# sliit_2019_V3.net
KiCad netlist of a schematic drawn in EAGLE
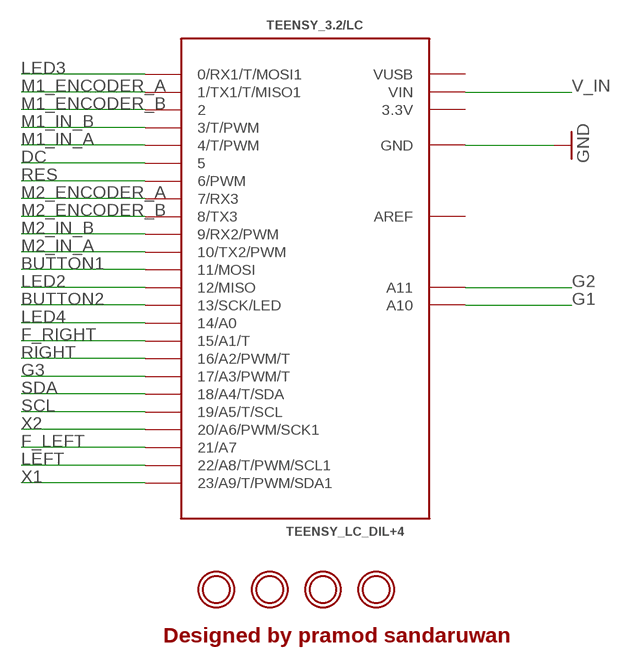
[diagram p0: schematic, sheet 1]
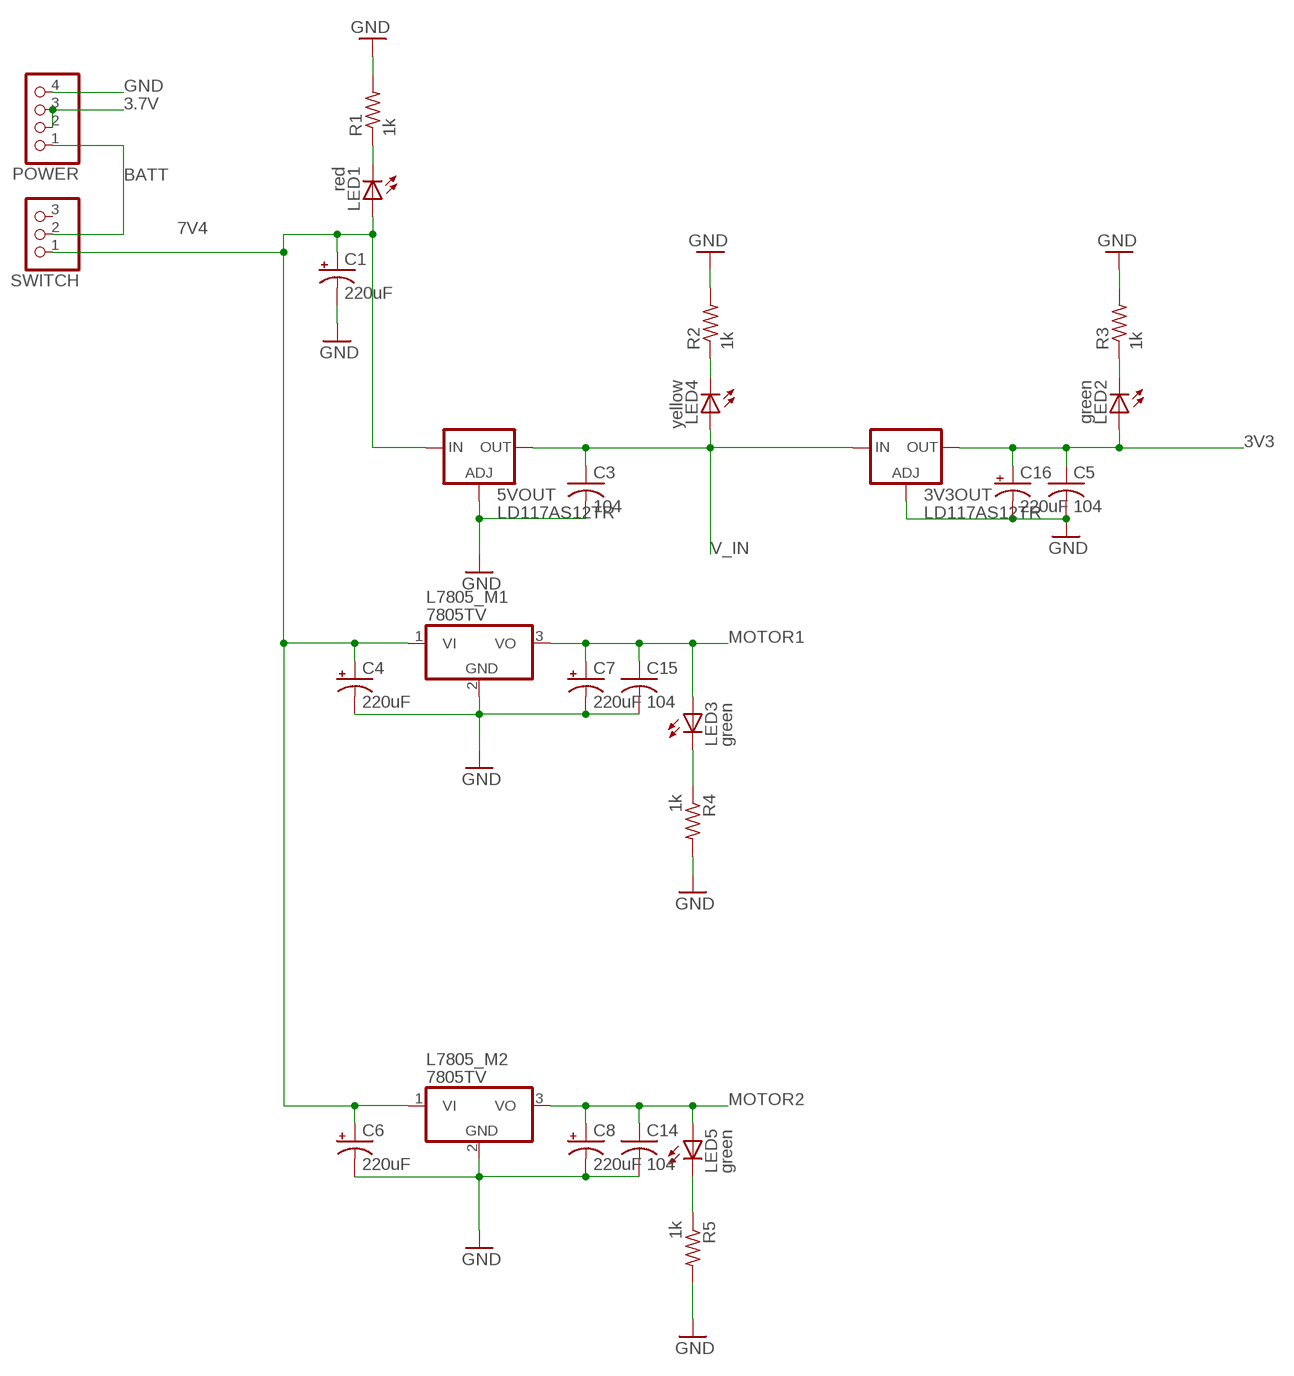
[diagram p1: schematic, sheet 2]
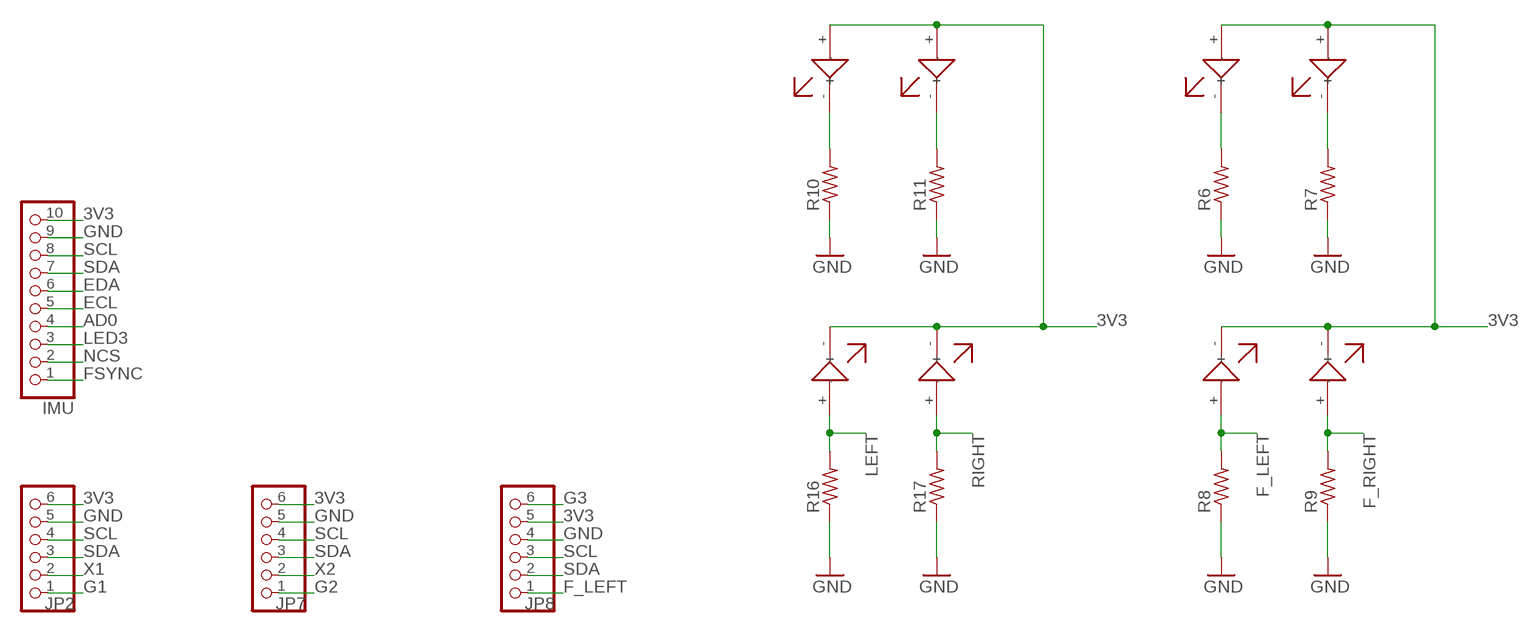
[diagram p2: schematic, sheet 3]
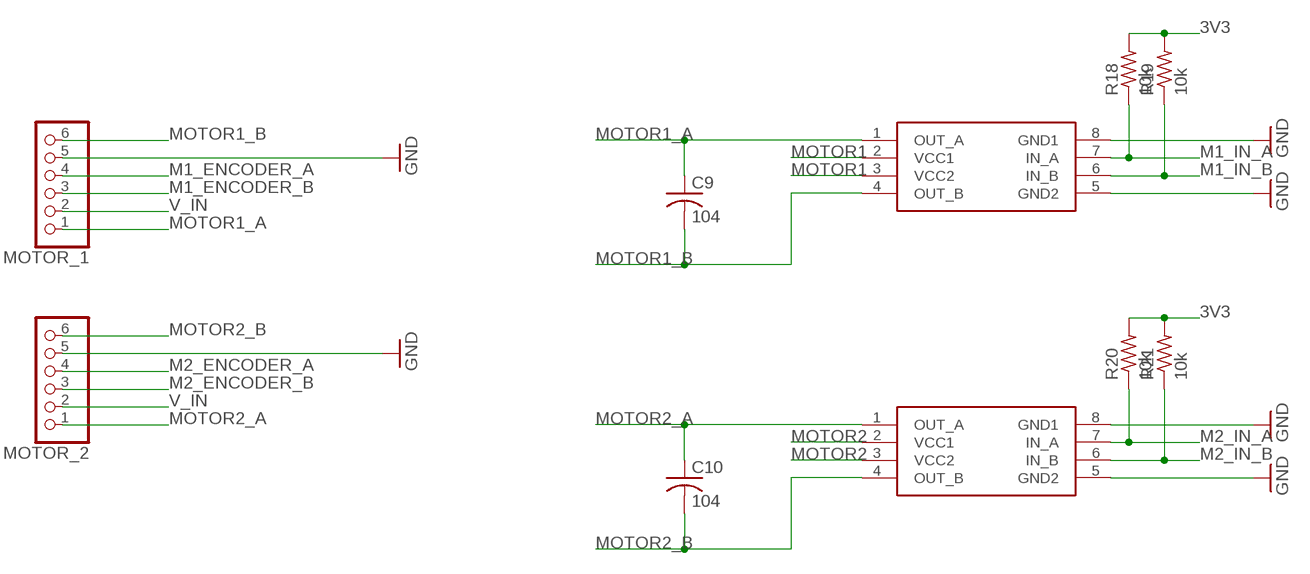
[diagram p3: schematic, sheet 4]
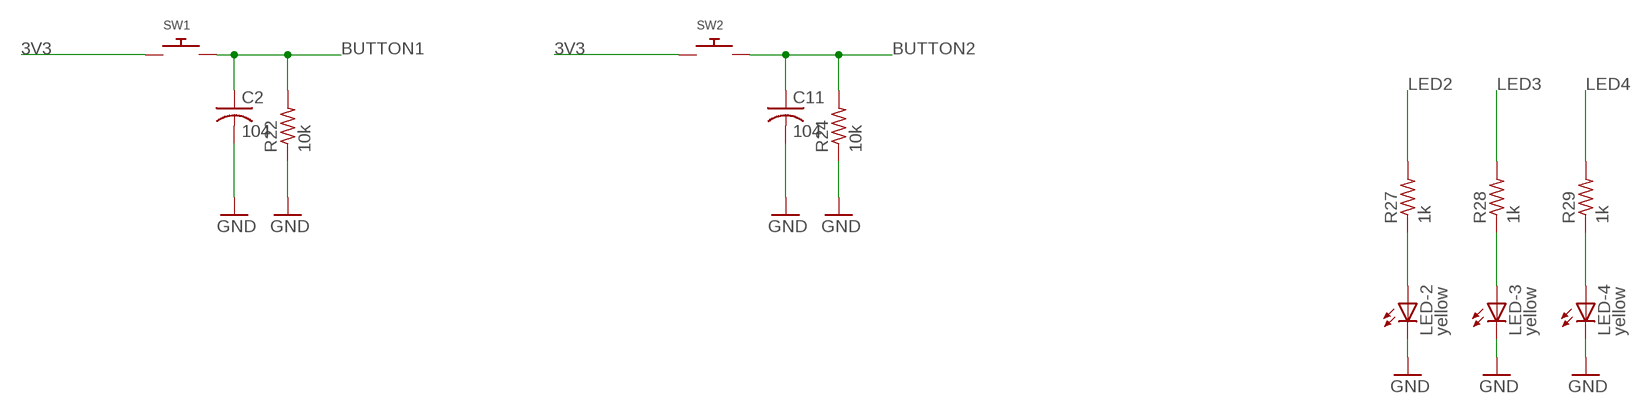
[diagram p4: schematic, sheet 5]
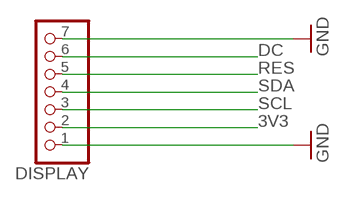
[diagram p5: schematic, sheet 6]

(export (version "E")
  (design (tool "Eeschema 10.0.6"))
  (components
    (comp (ref "TEENSY_3.2/LC")
      (value "TEENSY_LC_DIL+4")
      (footprint "eagle-import:TEENSY3-DIL+4")
      (libsource (lib "eagle-import") (part "TEENSY_LC_DIL+4"))
    )
    (comp (ref "U$7")
      (value "MOUNTINGHOLE2.5")
      (footprint "eagle-import:MOUNTINGHOLE_2.5_PLATED")
      (libsource (lib "eagle-import") (part "MOUNTINGHOLE2.5"))
    )
    (comp (ref "U$10")
      (value "MOUNTINGHOLE2.5")
      (footprint "eagle-import:MOUNTINGHOLE_2.5_PLATED")
      (libsource (lib "eagle-import") (part "MOUNTINGHOLE2.5"))
    )
    (comp (ref "U$11")
      (value "MOUNTINGHOLE2.5")
      (footprint "eagle-import:MOUNTINGHOLE_2.5_PLATED")
      (libsource (lib "eagle-import") (part "MOUNTINGHOLE2.5"))
    )
    (comp (ref "U$12")
      (value "MOUNTINGHOLE2.5")
      (footprint "eagle-import:MOUNTINGHOLE_2.5_PLATED")
      (libsource (lib "eagle-import") (part "MOUNTINGHOLE2.5"))
    )
    (comp (ref "C2")
      (value "104")
      (footprint "eagle-import:C1206")
      (libsource (lib "eagle-import") (part "resistor_348_C-USC1206"))
    )
    (comp (ref "C11")
      (value "104")
      (footprint "eagle-import:C1206")
      (libsource (lib "eagle-import") (part "resistor_348_C-USC1206"))
    )
    (comp (ref "LED-2")
      (value "yellow")
      (footprint "eagle-import:1206")
      (libsource (lib "eagle-import") (part "LEDSMT1206"))
    )
    (comp (ref "LED-3")
      (value "yellow")
      (footprint "eagle-import:1206")
      (libsource (lib "eagle-import") (part "LEDSMT1206"))
    )
    (comp (ref "LED-4")
      (value "yellow")
      (footprint "eagle-import:1206")
      (libsource (lib "eagle-import") (part "LEDSMT1206"))
    )
    (comp (ref "R22")
      (value "10k")
      (footprint "eagle-import:R1206")
      (libsource (lib "eagle-import") (part "rcl_334_R-US_R1206"))
    )
    (comp (ref "R24")
      (value "10k")
      (footprint "eagle-import:R1206")
      (libsource (lib "eagle-import") (part "rcl_334_R-US_R1206"))
    )
    (comp (ref "R27")
      (value "1k")
      (footprint "eagle-import:R1206")
      (libsource (lib "eagle-import") (part "rcl_334_R-US_R1206"))
    )
    (comp (ref "R28")
      (value "1k")
      (footprint "eagle-import:R1206")
      (libsource (lib "eagle-import") (part "rcl_334_R-US_R1206"))
    )
    (comp (ref "R29")
      (value "1k")
      (footprint "eagle-import:R1206")
      (libsource (lib "eagle-import") (part "rcl_334_R-US_R1206"))
    )
    (comp (ref "SW1")
      (value "SWITCH_PUSHBUTTONC&K_KSS")
      (footprint "eagle-import:BTN_CK_KSS")
      (libsource (lib "eagle-import") (part "SWITCH_PUSHBUTTONC&K_KSS"))
    )
    (comp (ref "SW2")
      (value "SWITCH_PUSHBUTTONC&K_KSS")
      (footprint "eagle-import:BTN_CK_KSS")
      (libsource (lib "eagle-import") (part "SWITCH_PUSHBUTTONC&K_KSS"))
    )
    (comp (ref "3V3OUT")
      (value "LD117AS12TR")
      (footprint "eagle-import:SOT223")
      (libsource (lib "eagle-import") (part "LD117A?S12TR"))
    )
    (comp (ref "5VOUT")
      (value "LD117AS12TR")
      (footprint "eagle-import:SOT223")
      (libsource (lib "eagle-import") (part "LD117A?S12TR"))
    )
    (comp (ref "C1")
      (value "220uF")
      (footprint "eagle-import:153CLV-0505")
      (libsource (lib "eagle-import") (part "CPOL-US153CLV-0505"))
    )
    (comp (ref "C3")
      (value "104")
      (footprint "eagle-import:C1206")
      (libsource (lib "eagle-import") (part "C-USC1206"))
    )
    (comp (ref "C4")
      (value "220uF")
      (footprint "eagle-import:153CLV-0505")
      (libsource (lib "eagle-import") (part "CPOL-US153CLV-0505"))
    )
    (comp (ref "C5")
      (value "104")
      (footprint "eagle-import:C1206")
      (libsource (lib "eagle-import") (part "C-USC1206"))
    )
    (comp (ref "C6")
      (value "220uF")
      (footprint "eagle-import:153CLV-0505")
      (libsource (lib "eagle-import") (part "CPOL-US153CLV-0505"))
    )
    (comp (ref "C7")
      (value "220uF")
      (footprint "eagle-import:153CLV-0505")
      (libsource (lib "eagle-import") (part "CPOL-US153CLV-0505"))
    )
    (comp (ref "C8")
      (value "220uF")
      (footprint "eagle-import:153CLV-0505")
      (libsource (lib "eagle-import") (part "CPOL-US153CLV-0505"))
    )
    (comp (ref "C14")
      (value "104")
      (footprint "eagle-import:C1206")
      (libsource (lib "eagle-import") (part "C-USC1206"))
    )
    (comp (ref "C15")
      (value "104")
      (footprint "eagle-import:C1206")
      (libsource (lib "eagle-import") (part "C-USC1206"))
    )
    (comp (ref "C16")
      (value "220uF")
      (footprint "eagle-import:153CLV-0505")
      (libsource (lib "eagle-import") (part "CPOL-US153CLV-0505"))
    )
    (comp (ref "L7805_M1")
      (value "7805TV")
      (footprint "eagle-import:TO220V")
      (libsource (lib "eagle-import") (part "78TV05"))
    )
    (comp (ref "L7805_M2")
      (value "7805TV")
      (footprint "eagle-import:TO220V")
      (libsource (lib "eagle-import") (part "78TV05"))
    )
    (comp (ref "LED1")
      (value "red")
      (footprint "eagle-import:1206")
      (libsource (lib "eagle-import") (part "LEDSMT1206"))
    )
    (comp (ref "LED2")
      (value "green")
      (footprint "eagle-import:1206")
      (libsource (lib "eagle-import") (part "LEDSMT1206"))
    )
    (comp (ref "LED3")
      (value "green")
      (footprint "eagle-import:1206")
      (libsource (lib "eagle-import") (part "LEDSMT1206"))
    )
    (comp (ref "LED4")
      (value "yellow")
      (footprint "eagle-import:1206")
      (libsource (lib "eagle-import") (part "LEDSMT1206"))
    )
    (comp (ref "LED5")
      (value "green")
      (footprint "eagle-import:1206")
      (libsource (lib "eagle-import") (part "LEDSMT1206"))
    )
    (comp (ref "POWER")
      (value "PINHD-1X4")
      (footprint "eagle-import:1X04")
      (libsource (lib "eagle-import") (part "PINHD-1X4"))
    )
    (comp (ref "R1")
      (value "1k")
      (footprint "eagle-import:R1206")
      (libsource (lib "eagle-import") (part "rcl_334_R-US_R1206"))
    )
    (comp (ref "R2")
      (value "1k")
      (footprint "eagle-import:R1206")
      (libsource (lib "eagle-import") (part "rcl_334_R-US_R1206"))
    )
    (comp (ref "R3")
      (value "1k")
      (footprint "eagle-import:R1206")
      (libsource (lib "eagle-import") (part "rcl_334_R-US_R1206"))
    )
    (comp (ref "R4")
      (value "1k")
      (footprint "eagle-import:R1206")
      (libsource (lib "eagle-import") (part "rcl_334_R-US_R1206"))
    )
    (comp (ref "R5")
      (value "1k")
      (footprint "eagle-import:R1206")
      (libsource (lib "eagle-import") (part "rcl_334_R-US_R1206"))
    )
    (comp (ref "SWITCH")
      (value "PINHD-1X3")
      (footprint "eagle-import:1X03")
      (libsource (lib "eagle-import") (part "PINHD-1X3"))
    )
    (comp (ref "C9")
      (value "104")
      (footprint "eagle-import:C1206")
      (libsource (lib "eagle-import") (part "resistor_348_C-USC1206"))
    )
    (comp (ref "C10")
      (value "104")
      (footprint "eagle-import:C1206")
      (libsource (lib "eagle-import") (part "resistor_348_C-USC1206"))
    )
    (comp (ref "MOTOR_1")
      (value "PINHD-1X6")
      (footprint "eagle-import:1X06")
      (libsource (lib "eagle-import") (part "PINHD-1X6"))
    )
    (comp (ref "MOTOR_2")
      (value "PINHD-1X6")
      (footprint "eagle-import:1X06")
      (libsource (lib "eagle-import") (part "PINHD-1X6"))
    )
    (comp (ref "R18")
      (value "10k")
      (footprint "eagle-import:R1206")
      (libsource (lib "eagle-import") (part "rcl_334_R-US_R1206"))
    )
    (comp (ref "R19")
      (value "10k")
      (footprint "eagle-import:R1206")
      (libsource (lib "eagle-import") (part "rcl_334_R-US_R1206"))
    )
    (comp (ref "R20")
      (value "10k")
      (footprint "eagle-import:R1206")
      (libsource (lib "eagle-import") (part "rcl_334_R-US_R1206"))
    )
    (comp (ref "R21")
      (value "10k")
      (footprint "eagle-import:R1206")
      (libsource (lib "eagle-import") (part "rcl_334_R-US_R1206"))
    )
    (comp (ref "U$2")
      (value "L9110")
      (footprint "eagle-import:L9110")
      (libsource (lib "eagle-import") (part "L9110"))
    )
    (comp (ref "U$3")
      (value "L9110")
      (footprint "eagle-import:L9110")
      (libsource (lib "eagle-import") (part "L9110"))
    )
    (comp (ref "DISPLAY")
      (value "PINHD-1X7")
      (footprint "eagle-import:1X07")
      (libsource (lib "eagle-import") (part "PINHD-1X7"))
    )
    (comp (ref "IMU")
      (value "PINHD-1X10")
      (footprint "eagle-import:1X10")
      (libsource (lib "eagle-import") (part "PINHD-1X10"))
    )
    (comp (ref "JP2")
      (value "PINHD-1X6")
      (footprint "eagle-import:1X06")
      (libsource (lib "eagle-import") (part "pinhead_325_PINHD-1X6"))
    )
    (comp (ref "JP7")
      (value "PINHD-1X6")
      (footprint "eagle-import:1X06")
      (libsource (lib "eagle-import") (part "pinhead_325_PINHD-1X6"))
    )
    (comp (ref "JP8")
      (value "PINHD-1X6")
      (footprint "eagle-import:1X06")
      (libsource (lib "eagle-import") (part "pinhead_325_PINHD-1X6"))
    )
    (comp (ref "R6")
      (value "R-US_R0805")
      (footprint "eagle-import:R0805")
      (libsource (lib "eagle-import") (part "R-US_R0805"))
    )
    (comp (ref "R7")
      (value "R-US_R0805")
      (footprint "eagle-import:R0805")
      (libsource (lib "eagle-import") (part "R-US_R0805"))
    )
    (comp (ref "R8")
      (value "R-US_R0805")
      (footprint "eagle-import:R0805")
      (libsource (lib "eagle-import") (part "R-US_R0805"))
    )
    (comp (ref "R9")
      (value "R-US_R0805")
      (footprint "eagle-import:R0805")
      (libsource (lib "eagle-import") (part "R-US_R0805"))
    )
    (comp (ref "R10")
      (value "R-US_R0805")
      (footprint "eagle-import:R0805")
      (libsource (lib "eagle-import") (part "R-US_R0805"))
    )
    (comp (ref "R11")
      (value "R-US_R0805")
      (footprint "eagle-import:R0805")
      (libsource (lib "eagle-import") (part "R-US_R0805"))
    )
    (comp (ref "R16")
      (value "R-US_R0805")
      (footprint "eagle-import:R0805")
      (libsource (lib "eagle-import") (part "R-US_R0805"))
    )
    (comp (ref "R17")
      (value "R-US_R0805")
      (footprint "eagle-import:R0805")
      (libsource (lib "eagle-import") (part "R-US_R0805"))
    )
    (comp (ref "U$1") (value "IR") (footprint "eagle-import:IR") (libsource (lib "eagle-import") (part "IR")))
    (comp (ref "U$4") (value "IR") (footprint "eagle-import:IR") (libsource (lib "eagle-import") (part "IR")))
    (comp (ref "U$5") (value "IR") (footprint "eagle-import:IR") (libsource (lib "eagle-import") (part "IR")))
    (comp (ref "U$6") (value "IR") (footprint "eagle-import:IR") (libsource (lib "eagle-import") (part "IR")))
    (comp (ref "U$8") (value "IR") (footprint "eagle-import:IR") (libsource (lib "eagle-import") (part "IR")))
    (comp (ref "U$9") (value "IR") (footprint "eagle-import:IR") (libsource (lib "eagle-import") (part "IR")))
    (comp (ref "U$14")
      (value "IR")
      (footprint "eagle-import:IR")
      (libsource (lib "eagle-import") (part "IR"))
    )
    (comp (ref "U$15")
      (value "IR")
      (footprint "eagle-import:IR")
      (libsource (lib "eagle-import") (part "IR"))
    )
  )
  (nets
    (net (code "1") (name "3.3V") (class "Default")
      (node (ref "TEENSY_3.2/LC") (pin "3.3V") (pinfunction "3.3V_3.3V") (pintype "power_in"))
    )
    (net (code "2") (name "3.7V") (class "Default")
      (node (ref "POWER") (pin "2") (pinfunction "2_2") (pintype "passive"))
      (node (ref "POWER") (pin "3") (pinfunction "3_3") (pintype "passive"))
    )
    (net (code "3") (name "3V3") (class "Default")
      (node (ref "3V3OUT") (pin "4") (pinfunction "OUT_4") (pintype "passive"))
      (node (ref "C16") (pin "+") (pinfunction "+_+") (pintype "passive"))
      (node (ref "C5") (pin "1") (pinfunction "1_1") (pintype "passive"))
      (node (ref "DISPLAY") (pin "2") (pinfunction "2_2") (pintype "passive"))
      (node (ref "IMU") (pin "10") (pinfunction "10_10") (pintype "passive"))
      (node (ref "JP2") (pin "6") (pinfunction "6_6") (pintype "passive"))
      (node (ref "JP7") (pin "6") (pinfunction "6_6") (pintype "passive"))
      (node (ref "JP8") (pin "5") (pinfunction "5_5") (pintype "passive"))
      (node (ref "LED2") (pin "A") (pinfunction "A_A") (pintype "passive"))
      (node (ref "R18") (pin "2") (pinfunction "2_2") (pintype "passive"))
      (node (ref "R19") (pin "2") (pinfunction "2_2") (pintype "passive"))
      (node (ref "R20") (pin "2") (pinfunction "2_2") (pintype "passive"))
      (node (ref "R21") (pin "2") (pinfunction "2_2") (pintype "passive"))
      (node (ref "SW1") (pin "P$1") (pinfunction "P$1_P$1") (pintype "passive"))
      (node (ref "SW2") (pin "P$1") (pinfunction "P$1_P$1") (pintype "passive"))
      (node (ref "U$1") (pin "+") (pinfunction "+_+") (pintype "bidirectional"))
      (node (ref "U$14") (pin "-") (pinfunction "-_-") (pintype "bidirectional"))
      (node (ref "U$15") (pin "-") (pinfunction "-_-") (pintype "bidirectional"))
      (node (ref "U$4") (pin "+") (pinfunction "+_+") (pintype "bidirectional"))
      (node (ref "U$5") (pin "-") (pinfunction "-_-") (pintype "bidirectional"))
      (node (ref "U$6") (pin "-") (pinfunction "-_-") (pintype "bidirectional"))
      (node (ref "U$8") (pin "+") (pinfunction "+_+") (pintype "bidirectional"))
      (node (ref "U$9") (pin "+") (pinfunction "+_+") (pintype "bidirectional"))
    )
    (net (code "4") (name "7V4") (class "Default")
      (node (ref "5VOUT") (pin "3") (pinfunction "IN_3") (pintype "input"))
      (node (ref "C1") (pin "+") (pinfunction "+_+") (pintype "passive"))
      (node (ref "C4") (pin "+") (pinfunction "+_+") (pintype "passive"))
      (node (ref "C6") (pin "+") (pinfunction "+_+") (pintype "passive"))
      (node (ref "L7805_M1") (pin "1") (pinfunction "VI_1") (pintype "input"))
      (node (ref "L7805_M2") (pin "1") (pinfunction "VI_1") (pintype "input"))
      (node (ref "LED1") (pin "A") (pinfunction "A_A") (pintype "passive"))
      (node (ref "SWITCH") (pin "1") (pinfunction "1_1") (pintype "passive"))
    )
    (net (code "5") (name "AD0") (class "Default")
      (node (ref "IMU") (pin "4") (pinfunction "4_4") (pintype "passive"))
    )
    (net (code "6") (name "AREF") (class "Default")
      (node (ref "TEENSY_3.2/LC") (pin "AREF") (pinfunction "AREF_AREF") (pintype "power_in"))
    )
    (net (code "7") (name "BATT") (class "Default")
      (node (ref "POWER") (pin "1") (pinfunction "1_1") (pintype "passive"))
      (node (ref "SWITCH") (pin "2") (pinfunction "2_2") (pintype "passive"))
    )
    (net (code "8") (name "BUTTON1") (class "Default")
      (node (ref "C2") (pin "1") (pinfunction "1_1") (pintype "passive"))
      (node (ref "R22") (pin "2") (pinfunction "2_2") (pintype "passive"))
      (node (ref "SW1") (pin "P$2") (pinfunction "P$2_P$2") (pintype "passive"))
      (node (ref "TEENSY_3.2/LC") (pin "11") (pinfunction "11/MOSI_11") (pintype "bidirectional"))
    )
    (net (code "9") (name "BUTTON2") (class "Default")
      (node (ref "C11") (pin "1") (pinfunction "1_1") (pintype "passive"))
      (node (ref "R24") (pin "2") (pinfunction "2_2") (pintype "passive"))
      (node (ref "SW2") (pin "P$2") (pinfunction "P$2_P$2") (pintype "passive"))
      (node (ref "TEENSY_3.2/LC") (pin "13") (pinfunction "13/SCK/LED_13") (pintype "bidirectional"))
    )
    (net (code "10") (name "DC") (class "Default")
      (node (ref "DISPLAY") (pin "6") (pinfunction "6_6") (pintype "passive"))
      (node (ref "TEENSY_3.2/LC") (pin "5") (pinfunction "5_5") (pintype "bidirectional"))
    )
    (net (code "11") (name "ECL") (class "Default")
      (node (ref "IMU") (pin "5") (pinfunction "5_5") (pintype "passive"))
    )
    (net (code "12") (name "EDA") (class "Default")
      (node (ref "IMU") (pin "6") (pinfunction "6_6") (pintype "passive"))
    )
    (net (code "13") (name "FSYNC") (class "Default")
      (node (ref "IMU") (pin "1") (pinfunction "1_1") (pintype "passive"))
    )
    (net (code "14") (name "F_LEFT") (class "Default")
      (node (ref "JP8") (pin "1") (pinfunction "1_1") (pintype "passive"))
      (node (ref "R8") (pin "2") (pinfunction "2_2") (pintype "passive"))
      (node (ref "TEENSY_3.2/LC") (pin "21/A7") (pinfunction "21/A7_21/A7") (pintype "bidirectional"))
      (node (ref "U$5") (pin "+") (pinfunction "+_+") (pintype "bidirectional"))
    )
    (net (code "15") (name "F_RIGHT") (class "Default")
      (node (ref "R9") (pin "2") (pinfunction "2_2") (pintype "passive"))
      (node (ref "TEENSY_3.2/LC") (pin "15/A1") (pinfunction "15/A1/T_15/A1") (pintype "bidirectional"))
      (node (ref "U$6") (pin "+") (pinfunction "+_+") (pintype "bidirectional"))
    )
    (net (code "16") (name "G1") (class "Default")
      (node (ref "JP2") (pin "1") (pinfunction "1_1") (pintype "passive"))
      (node (ref "TEENSY_3.2/LC") (pin "A10") (pinfunction "A10_A10") (pintype "bidirectional"))
    )
    (net (code "17") (name "G2") (class "Default")
      (node (ref "JP7") (pin "1") (pinfunction "1_1") (pintype "passive"))
      (node (ref "TEENSY_3.2/LC") (pin "A11") (pinfunction "A11_A11") (pintype "bidirectional"))
    )
    (net (code "18") (name "G3") (class "Default")
      (node (ref "JP8") (pin "6") (pinfunction "6_6") (pintype "passive"))
      (node (ref "TEENSY_3.2/LC") (pin "17/A3") (pinfunction "17/A3/PWM/T_17/A3") (pintype "bidirectional"))
    )
    (net (code "19") (name "GND") (class "Default")
      (node (ref "3V3OUT") (pin "1") (pinfunction "ADJ_1") (pintype "input"))
      (node (ref "5VOUT") (pin "1") (pinfunction "ADJ_1") (pintype "input"))
      (node (ref "C1") (pin "-") (pinfunction "-_-") (pintype "passive"))
      (node (ref "C11") (pin "2") (pinfunction "2_2") (pintype "passive"))
      (node (ref "C14") (pin "2") (pinfunction "2_2") (pintype "passive"))
      (node (ref "C15") (pin "2") (pinfunction "2_2") (pintype "passive"))
      (node (ref "C16") (pin "-") (pinfunction "-_-") (pintype "passive"))
      (node (ref "C2") (pin "2") (pinfunction "2_2") (pintype "passive"))
      (node (ref "C3") (pin "2") (pinfunction "2_2") (pintype "passive"))
      (node (ref "C4") (pin "-") (pinfunction "-_-") (pintype "passive"))
      (node (ref "C5") (pin "2") (pinfunction "2_2") (pintype "passive"))
      (node (ref "C6") (pin "-") (pinfunction "-_-") (pintype "passive"))
      (node (ref "C7") (pin "-") (pinfunction "-_-") (pintype "passive"))
      (node (ref "C8") (pin "-") (pinfunction "-_-") (pintype "passive"))
      (node (ref "DISPLAY") (pin "1") (pinfunction "1_1") (pintype "passive"))
      (node (ref "DISPLAY") (pin "7") (pinfunction "7_7") (pintype "passive"))
      (node (ref "IMU") (pin "9") (pinfunction "9_9") (pintype "passive"))
      (node (ref "JP2") (pin "5") (pinfunction "5_5") (pintype "passive"))
      (node (ref "JP7") (pin "5") (pinfunction "5_5") (pintype "passive"))
      (node (ref "JP8") (pin "4") (pinfunction "4_4") (pintype "passive"))
      (node (ref "L7805_M1") (pin "2") (pinfunction "GND_2") (pintype "passive"))
      (node (ref "L7805_M2") (pin "2") (pinfunction "GND_2") (pintype "passive"))
      (node (ref "LED-2") (pin "C") (pinfunction "C_C") (pintype "passive"))
      (node (ref "LED-3") (pin "C") (pinfunction "C_C") (pintype "passive"))
      (node (ref "LED-4") (pin "C") (pinfunction "C_C") (pintype "passive"))
      (node (ref "MOTOR_1") (pin "5") (pinfunction "5_5") (pintype "passive"))
      (node (ref "MOTOR_2") (pin "5") (pinfunction "5_5") (pintype "passive"))
      (node (ref "POWER") (pin "4") (pinfunction "4_4") (pintype "passive"))
      (node (ref "R1") (pin "2") (pinfunction "2_2") (pintype "passive"))
      (node (ref "R10") (pin "1") (pinfunction "1_1") (pintype "passive"))
      (node (ref "R11") (pin "1") (pinfunction "1_1") (pintype "passive"))
      (node (ref "R16") (pin "1") (pinfunction "1_1") (pintype "passive"))
      (node (ref "R17") (pin "1") (pinfunction "1_1") (pintype "passive"))
      (node (ref "R2") (pin "2") (pinfunction "2_2") (pintype "passive"))
      (node (ref "R22") (pin "1") (pinfunction "1_1") (pintype "passive"))
      (node (ref "R24") (pin "1") (pinfunction "1_1") (pintype "passive"))
      (node (ref "R3") (pin "2") (pinfunction "2_2") (pintype "passive"))
      (node (ref "R4") (pin "2") (pinfunction "2_2") (pintype "passive"))
      (node (ref "R5") (pin "2") (pinfunction "2_2") (pintype "passive"))
      (node (ref "R6") (pin "1") (pinfunction "1_1") (pintype "passive"))
      (node (ref "R7") (pin "1") (pinfunction "1_1") (pintype "passive"))
      (node (ref "R8") (pin "1") (pinfunction "1_1") (pintype "passive"))
      (node (ref "R9") (pin "1") (pinfunction "1_1") (pintype "passive"))
      (node (ref "TEENSY_3.2/LC") (pin "AGND") (pinfunction "GND_AGND") (pintype "power_in"))
      (node (ref "TEENSY_3.2/LC") (pin "GND") (pinfunction "GND_GND") (pintype "power_in"))
      (node (ref "U$2") (pin "5") (pinfunction "GND2_5") (pintype "bidirectional"))
      (node (ref "U$2") (pin "8") (pinfunction "GND1_8") (pintype "bidirectional"))
      (node (ref "U$3") (pin "5") (pinfunction "GND2_5") (pintype "bidirectional"))
      (node (ref "U$3") (pin "8") (pinfunction "GND1_8") (pintype "bidirectional"))
    )
    (net (code "20") (name "LED2") (class "Default")
      (node (ref "R27") (pin "2") (pinfunction "2_2") (pintype "passive"))
      (node (ref "TEENSY_3.2/LC") (pin "12") (pinfunction "12/MISO_12") (pintype "bidirectional"))
    )
    (net (code "21") (name "LED3") (class "Default")
      (node (ref "IMU") (pin "3") (pinfunction "3_3") (pintype "passive"))
      (node (ref "R28") (pin "2") (pinfunction "2_2") (pintype "passive"))
      (node (ref "TEENSY_3.2/LC") (pin "0") (pinfunction "0/RX1/T/MOSI1_0") (pintype "bidirectional"))
    )
    (net (code "22") (name "LED4") (class "Default")
      (node (ref "R29") (pin "2") (pinfunction "2_2") (pintype "passive"))
      (node (ref "TEENSY_3.2/LC") (pin "14/A0") (pinfunction "14/A0_14/A0") (pintype "bidirectional"))
    )
    (net (code "23") (name "LEFT") (class "Default")
      (node (ref "R16") (pin "2") (pinfunction "2_2") (pintype "passive"))
      (node (ref "TEENSY_3.2/LC") (pin "22/A8") (pinfunction "22/A8/T/PWM/SCL1_22/A8") (pintype "bidirectional"))
      (node (ref "U$14") (pin "+") (pinfunction "+_+") (pintype "bidirectional"))
    )
    (net (code "24") (name "M1_ENCODER_A") (class "Default")
      (node (ref "MOTOR_1") (pin "4") (pinfunction "4_4") (pintype "passive"))
      (node (ref "TEENSY_3.2/LC") (pin "1") (pinfunction "1/TX1/T/MISO1_1") (pintype "bidirectional"))
    )
    (net (code "25") (name "M1_ENCODER_B") (class "Default")
      (node (ref "MOTOR_1") (pin "3") (pinfunction "3_3") (pintype "passive"))
      (node (ref "TEENSY_3.2/LC") (pin "2") (pinfunction "2_2") (pintype "bidirectional"))
    )
    (net (code "26") (name "M1_IN_A") (class "Default")
      (node (ref "R18") (pin "1") (pinfunction "1_1") (pintype "passive"))
      (node (ref "TEENSY_3.2/LC") (pin "4") (pinfunction "4/T/PWM_4") (pintype "bidirectional"))
      (node (ref "U$2") (pin "7") (pinfunction "IN_A_7") (pintype "bidirectional"))
    )
    (net (code "27") (name "M1_IN_B") (class "Default")
      (node (ref "R19") (pin "1") (pinfunction "1_1") (pintype "passive"))
      (node (ref "TEENSY_3.2/LC") (pin "3") (pinfunction "3/T/PWM_3") (pintype "bidirectional"))
      (node (ref "U$2") (pin "6") (pinfunction "IN_B_6") (pintype "bidirectional"))
    )
    (net (code "28") (name "M2_ENCODER_A") (class "Default")
      (node (ref "MOTOR_2") (pin "4") (pinfunction "4_4") (pintype "passive"))
      (node (ref "TEENSY_3.2/LC") (pin "7") (pinfunction "7/RX3_7") (pintype "bidirectional"))
    )
    (net (code "29") (name "M2_ENCODER_B") (class "Default")
      (node (ref "MOTOR_2") (pin "3") (pinfunction "3_3") (pintype "passive"))
      (node (ref "TEENSY_3.2/LC") (pin "8") (pinfunction "8/TX3_8") (pintype "bidirectional"))
    )
    (net (code "30") (name "M2_IN_A") (class "Default")
      (node (ref "R20") (pin "1") (pinfunction "1_1") (pintype "passive"))
      (node (ref "TEENSY_3.2/LC") (pin "10") (pinfunction "10/TX2/PWM_10") (pintype "bidirectional"))
      (node (ref "U$3") (pin "7") (pinfunction "IN_A_7") (pintype "bidirectional"))
    )
    (net (code "31") (name "M2_IN_B") (class "Default")
      (node (ref "R21") (pin "1") (pinfunction "1_1") (pintype "passive"))
      (node (ref "TEENSY_3.2/LC") (pin "9") (pinfunction "9/RX2/PWM_9") (pintype "bidirectional"))
      (node (ref "U$3") (pin "6") (pinfunction "IN_B_6") (pintype "bidirectional"))
    )
    (net (code "32") (name "MOTOR1") (class "Default")
      (node (ref "C15") (pin "1") (pinfunction "1_1") (pintype "passive"))
      (node (ref "C7") (pin "+") (pinfunction "+_+") (pintype "passive"))
      (node (ref "L7805_M1") (pin "3") (pinfunction "VO_3") (pintype "passive"))
      (node (ref "LED3") (pin "A") (pinfunction "A_A") (pintype "passive"))
      (node (ref "U$2") (pin "2") (pinfunction "VCC1_2") (pintype "bidirectional"))
      (node (ref "U$2") (pin "3") (pinfunction "VCC2_3") (pintype "bidirectional"))
    )
    (net (code "33") (name "MOTOR1_A") (class "Default")
      (node (ref "C9") (pin "1") (pinfunction "1_1") (pintype "passive"))
      (node (ref "MOTOR_1") (pin "1") (pinfunction "1_1") (pintype "passive"))
      (node (ref "U$2") (pin "1") (pinfunction "OUT_A_1") (pintype "bidirectional"))
    )
    (net (code "34") (name "MOTOR1_B") (class "Default")
      (node (ref "C9") (pin "2") (pinfunction "2_2") (pintype "passive"))
      (node (ref "MOTOR_1") (pin "6") (pinfunction "6_6") (pintype "passive"))
      (node (ref "U$2") (pin "4") (pinfunction "OUT_B_4") (pintype "bidirectional"))
    )
    (net (code "35") (name "MOTOR2") (class "Default")
      (node (ref "C14") (pin "1") (pinfunction "1_1") (pintype "passive"))
      (node (ref "C8") (pin "+") (pinfunction "+_+") (pintype "passive"))
      (node (ref "L7805_M2") (pin "3") (pinfunction "VO_3") (pintype "passive"))
      (node (ref "LED5") (pin "A") (pinfunction "A_A") (pintype "passive"))
      (node (ref "U$3") (pin "2") (pinfunction "VCC1_2") (pintype "bidirectional"))
      (node (ref "U$3") (pin "3") (pinfunction "VCC2_3") (pintype "bidirectional"))
    )
    (net (code "36") (name "MOTOR2_A") (class "Default")
      (node (ref "C10") (pin "1") (pinfunction "1_1") (pintype "passive"))
      (node (ref "MOTOR_2") (pin "1") (pinfunction "1_1") (pintype "passive"))
      (node (ref "U$3") (pin "1") (pinfunction "OUT_A_1") (pintype "bidirectional"))
    )
    (net (code "37") (name "MOTOR2_B") (class "Default")
      (node (ref "C10") (pin "2") (pinfunction "2_2") (pintype "passive"))
      (node (ref "MOTOR_2") (pin "6") (pinfunction "6_6") (pintype "passive"))
      (node (ref "U$3") (pin "4") (pinfunction "OUT_B_4") (pintype "bidirectional"))
    )
    (net (code "38") (name "NCS") (class "Default")
      (node (ref "IMU") (pin "2") (pinfunction "2_2") (pintype "passive"))
    )
    (net (code "39") (name "Net-(LED-2-PadA)") (class "Default")
      (node (ref "LED-2") (pin "A") (pinfunction "A_A") (pintype "passive"))
      (node (ref "R27") (pin "1") (pinfunction "1_1") (pintype "passive"))
    )
    (net (code "40") (name "Net-(LED-3-PadA)") (class "Default")
      (node (ref "LED-3") (pin "A") (pinfunction "A_A") (pintype "passive"))
      (node (ref "R28") (pin "1") (pinfunction "1_1") (pintype "passive"))
    )
    (net (code "41") (name "Net-(LED-4-PadA)") (class "Default")
      (node (ref "LED-4") (pin "A") (pinfunction "A_A") (pintype "passive"))
      (node (ref "R29") (pin "1") (pinfunction "1_1") (pintype "passive"))
    )
    (net (code "42") (name "Net-(LED1-PadC)") (class "Default")
      (node (ref "LED1") (pin "C") (pinfunction "C_C") (pintype "passive"))
      (node (ref "R1") (pin "1") (pinfunction "1_1") (pintype "passive"))
    )
    (net (code "43") (name "Net-(LED2-PadC)") (class "Default")
      (node (ref "LED2") (pin "C") (pinfunction "C_C") (pintype "passive"))
      (node (ref "R3") (pin "1") (pinfunction "1_1") (pintype "passive"))
    )
    (net (code "44") (name "Net-(LED3-PadC)") (class "Default")
      (node (ref "LED3") (pin "C") (pinfunction "C_C") (pintype "passive"))
      (node (ref "R4") (pin "1") (pinfunction "1_1") (pintype "passive"))
    )
    (net (code "45") (name "Net-(LED4-PadC)") (class "Default")
      (node (ref "LED4") (pin "C") (pinfunction "C_C") (pintype "passive"))
      (node (ref "R2") (pin "1") (pinfunction "1_1") (pintype "passive"))
    )
    (net (code "46") (name "Net-(LED5-PadC)") (class "Default")
      (node (ref "LED5") (pin "C") (pinfunction "C_C") (pintype "passive"))
      (node (ref "R5") (pin "1") (pinfunction "1_1") (pintype "passive"))
    )
    (net (code "47") (name "Net-(R6-Pad2)") (class "Default")
      (node (ref "R6") (pin "2") (pinfunction "2_2") (pintype "passive"))
      (node (ref "U$1") (pin "-") (pinfunction "-_-") (pintype "bidirectional"))
    )
    (net (code "48") (name "Net-(R7-Pad2)") (class "Default")
      (node (ref "R7") (pin "2") (pinfunction "2_2") (pintype "passive"))
      (node (ref "U$4") (pin "-") (pinfunction "-_-") (pintype "bidirectional"))
    )
    (net (code "49") (name "Net-(R10-Pad2)") (class "Default")
      (node (ref "R10") (pin "2") (pinfunction "2_2") (pintype "passive"))
      (node (ref "U$8") (pin "-") (pinfunction "-_-") (pintype "bidirectional"))
    )
    (net (code "50") (name "Net-(R11-Pad2)") (class "Default")
      (node (ref "R11") (pin "2") (pinfunction "2_2") (pintype "passive"))
      (node (ref "U$9") (pin "-") (pinfunction "-_-") (pintype "bidirectional"))
    )
    (net (code "51") (name "RES") (class "Default")
      (node (ref "DISPLAY") (pin "5") (pinfunction "5_5") (pintype "passive"))
      (node (ref "TEENSY_3.2/LC") (pin "6") (pinfunction "6/PWM_6") (pintype "bidirectional"))
    )
    (net (code "52") (name "RIGHT") (class "Default")
      (node (ref "R17") (pin "2") (pinfunction "2_2") (pintype "passive"))
      (node (ref "TEENSY_3.2/LC") (pin "16/A2") (pinfunction "16/A2/PWM/T_16/A2") (pintype "bidirectional"))
      (node (ref "U$15") (pin "+") (pinfunction "+_+") (pintype "bidirectional"))
    )
    (net (code "53") (name "SCL") (class "Default")
      (node (ref "DISPLAY") (pin "3") (pinfunction "3_3") (pintype "passive"))
      (node (ref "IMU") (pin "8") (pinfunction "8_8") (pintype "passive"))
      (node (ref "JP2") (pin "4") (pinfunction "4_4") (pintype "passive"))
      (node (ref "JP7") (pin "4") (pinfunction "4_4") (pintype "passive"))
      (node (ref "JP8") (pin "3") (pinfunction "3_3") (pintype "passive"))
      (node (ref "TEENSY_3.2/LC") (pin "19/A5") (pinfunction "19/A5/T/SCL_19/A5") (pintype "bidirectional"))
    )
    (net (code "54") (name "SDA") (class "Default")
      (node (ref "DISPLAY") (pin "4") (pinfunction "4_4") (pintype "passive"))
      (node (ref "IMU") (pin "7") (pinfunction "7_7") (pintype "passive"))
      (node (ref "JP2") (pin "3") (pinfunction "3_3") (pintype "passive"))
      (node (ref "JP7") (pin "3") (pinfunction "3_3") (pintype "passive"))
      (node (ref "JP8") (pin "2") (pinfunction "2_2") (pintype "passive"))
      (node (ref "TEENSY_3.2/LC") (pin "18/A4") (pinfunction "18/A4/T/SDA_18/A4") (pintype "bidirectional"))
    )
    (net (code "55") (name "VUSB") (class "Default")
      (node (ref "TEENSY_3.2/LC") (pin "VUSB") (pinfunction "VUSB_VUSB") (pintype "power_in"))
    )
    (net (code "56") (name "V_IN") (class "Default")
      (node (ref "3V3OUT") (pin "3") (pinfunction "IN_3") (pintype "input"))
      (node (ref "5VOUT") (pin "4") (pinfunction "OUT_4") (pintype "passive"))
      (node (ref "C3") (pin "1") (pinfunction "1_1") (pintype "passive"))
      (node (ref "LED4") (pin "A") (pinfunction "A_A") (pintype "passive"))
      (node (ref "MOTOR_1") (pin "2") (pinfunction "2_2") (pintype "passive"))
      (node (ref "MOTOR_2") (pin "2") (pinfunction "2_2") (pintype "passive"))
      (node (ref "TEENSY_3.2/LC") (pin "VIN") (pinfunction "VIN_VIN") (pintype "power_in"))
    )
    (net (code "57") (name "X1") (class "Default")
      (node (ref "JP2") (pin "2") (pinfunction "2_2") (pintype "passive"))
      (node (ref "TEENSY_3.2/LC") (pin "23/A9") (pinfunction "23/A9/T/PWM/SDA1_23/A9") (pintype "bidirectional"))
    )
    (net (code "58") (name "X2") (class "Default")
      (node (ref "JP7") (pin "2") (pinfunction "2_2") (pintype "passive"))
      (node (ref "TEENSY_3.2/LC") (pin "20/A6") (pinfunction "20/A6/PWM/SCK1_20/A6") (pintype "bidirectional"))
    )
    (net (code "59") (name "unconnected-(SWITCH-Pad3)") (class "Default")
      (node (ref "SWITCH") (pin "3") (pinfunction "3_3") (pintype "passive"))
    )
  )
)
